# Wii_Board.net
KiCad netlist of a schematic drawn in EAGLE
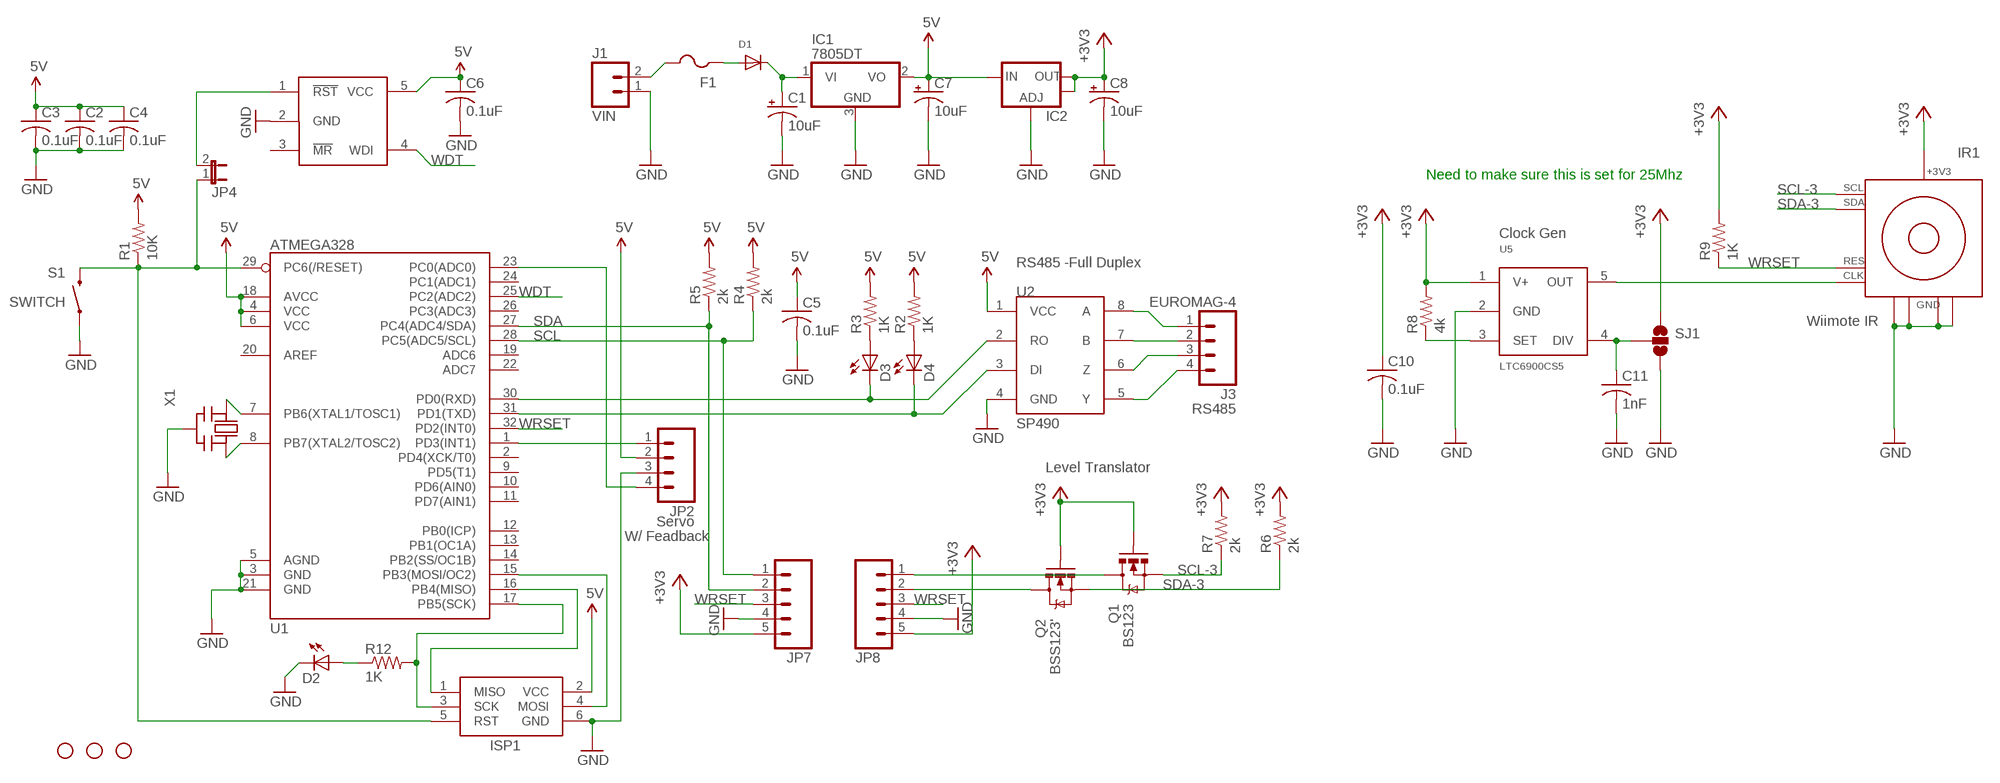
[diagram p0: schematic, sheet 1]

(export (version "E")
  (design (tool "Eeschema 10.0.6"))
  (components
    (comp (ref "C1")
      (value "10uF")
      (footprint "eagle-import:CT6032")
      (libsource (lib "eagle-import") (part "CPOL-USCT6032"))
    )
    (comp (ref "C2")
      (value "0.1uF")
      (footprint "eagle-import:C0805")
      (libsource (lib "eagle-import") (part "C-USC0805"))
    )
    (comp (ref "C3")
      (value "0.1uF")
      (footprint "eagle-import:C0805")
      (libsource (lib "eagle-import") (part "C-USC0805"))
    )
    (comp (ref "C4")
      (value "0.1uF")
      (footprint "eagle-import:C0805")
      (libsource (lib "eagle-import") (part "C-USC0805"))
    )
    (comp (ref "C5")
      (value "0.1uF")
      (footprint "eagle-import:C0805")
      (libsource (lib "eagle-import") (part "C-USC0805"))
    )
    (comp (ref "C6")
      (value "0.1uF")
      (footprint "eagle-import:C0805")
      (libsource (lib "eagle-import") (part "C-USC0805"))
    )
    (comp (ref "C7")
      (value "10uF")
      (footprint "eagle-import:CT3216")
      (libsource (lib "eagle-import") (part "CPOL-USCT3216"))
    )
    (comp (ref "C8")
      (value "10uF")
      (footprint "eagle-import:CT3528")
      (libsource (lib "eagle-import") (part "CPOL-USCT3528"))
    )
    (comp (ref "C10")
      (value "0.1uF")
      (footprint "eagle-import:C0805")
      (libsource (lib "eagle-import") (part "C-USC0805"))
    )
    (comp (ref "C11")
      (value "1nF")
      (footprint "eagle-import:C0805")
      (libsource (lib "eagle-import") (part "C-USC0805"))
    )
    (comp (ref "D1")
      (value "DIODESMA")
      (footprint "eagle-import:SMADIODE")
      (libsource (lib "eagle-import") (part "DIODESMA"))
    )
    (comp (ref "D2")
      (value "LEDCHIPLED_0805")
      (footprint "eagle-import:CHIPLED_0805")
      (libsource (lib "eagle-import") (part "LEDCHIPLED_0805"))
    )
    (comp (ref "D3")
      (value "LEDCHIPLED_0805")
      (footprint "eagle-import:CHIPLED_0805")
      (libsource (lib "eagle-import") (part "LEDCHIPLED_0805"))
    )
    (comp (ref "D4")
      (value "LEDCHIPLED_0805")
      (footprint "eagle-import:CHIPLED_0805")
      (libsource (lib "eagle-import") (part "LEDCHIPLED_0805"))
    )
    (comp (ref "F1")
      (value "PTCFUSE-1206")
      (footprint "eagle-import:R1206")
      (libsource (lib "eagle-import") (part "PTCFUSE-1206"))
    )
    (comp (ref "IC1")
      (value "7805DT")
      (footprint "eagle-import:TO252")
      (libsource (lib "eagle-import") (part "78DT05"))
    )
    (comp (ref "IC2")
      (value "V_REG_LM1117SOT223")
      (footprint "eagle-import:SOT223")
      (libsource (lib "eagle-import") (part "V_REG_LM1117SOT223"))
    )
    (comp (ref "IR1")
      (value "Wiimote IR")
      (footprint "eagle-import:WII_IR_SENSOR")
      (libsource (lib "eagle-import") (part "WII_IR_SENSOR"))
    )
    (comp (ref "ISP1")
      (value "AVRISP-6")
      (footprint "eagle-import:AVRISP")
      (libsource (lib "eagle-import") (part "AVRISP-6"))
    )
    (comp (ref "J1")
      (value "VIN")
      (footprint "eagle-import:M2")
      (libsource (lib "eagle-import") (part "EUROMAG-290DEG"))
    )
    (comp (ref "J3")
      (value "EUROMAG-4")
      (footprint "eagle-import:M4")
      (libsource (lib "eagle-import") (part "EUROMAG-4"))
    )
    (comp (ref "JP1")
      (value "STAND-OFF")
      (footprint "eagle-import:STAND-OFF")
      (libsource (lib "eagle-import") (part "STAND-OFF"))
    )
    (comp (ref "JP2")
      (value "M04LOCK")
      (footprint "eagle-import:1X04_LOCK")
      (libsource (lib "eagle-import") (part "M04LOCK"))
    )
    (comp (ref "JP3")
      (value "STAND-OFF")
      (footprint "eagle-import:STAND-OFF")
      (libsource (lib "eagle-import") (part "STAND-OFF"))
    )
    (comp (ref "JP4")
      (value "JUMPER-2SMD-NO")
      (footprint "eagle-import:SJ_2S-NO")
      (libsource (lib "eagle-import") (part "JUMPER-2SMD-NO"))
    )
    (comp (ref "JP5")
      (value "STAND-OFF")
      (footprint "eagle-import:STAND-OFF")
      (libsource (lib "eagle-import") (part "STAND-OFF"))
    )
    (comp (ref "JP7")
      (value "M05LOCK_LONGPADS")
      (footprint "eagle-import:1X05_LOCK_LONGPADS")
      (libsource (lib "eagle-import") (part "M05LOCK_LONGPADS"))
    )
    (comp (ref "JP8")
      (value "M05LOCK_LONGPADS")
      (footprint "eagle-import:1X05_LOCK_LONGPADS")
      (libsource (lib "eagle-import") (part "M05LOCK_LONGPADS"))
    )
    (comp (ref "Q1")
      (value "BS123")
      (footprint "eagle-import:SOT23")
      (libsource (lib "eagle-import") (part "MOSFET-NCHANNELBSS123LT1G"))
    )
    (comp (ref "Q2")
      (value "BSS123'")
      (footprint "eagle-import:SOT23")
      (libsource (lib "eagle-import") (part "MOSFET-NCHANNELBSS123LT1G"))
    )
    (comp (ref "R1")
      (value "10K")
      (footprint "eagle-import:M0805")
      (libsource (lib "eagle-import") (part "R-US_M0805"))
    )
    (comp (ref "R2")
      (value "1K")
      (footprint "eagle-import:M0805")
      (libsource (lib "eagle-import") (part "R-US_M0805"))
    )
    (comp (ref "R3")
      (value "1K")
      (footprint "eagle-import:M0805")
      (libsource (lib "eagle-import") (part "R-US_M0805"))
    )
    (comp (ref "R4")
      (value "2k")
      (footprint "eagle-import:M0805")
      (libsource (lib "eagle-import") (part "R-US_M0805"))
    )
    (comp (ref "R5")
      (value "2k")
      (footprint "eagle-import:M0805")
      (libsource (lib "eagle-import") (part "R-US_M0805"))
    )
    (comp (ref "R6")
      (value "2k")
      (footprint "eagle-import:M0805")
      (libsource (lib "eagle-import") (part "R-US_M0805"))
    )
    (comp (ref "R7")
      (value "2k")
      (footprint "eagle-import:M0805")
      (libsource (lib "eagle-import") (part "R-US_M0805"))
    )
    (comp (ref "R8")
      (value "4k")
      (footprint "eagle-import:M0805")
      (libsource (lib "eagle-import") (part "R-US_M0805"))
    )
    (comp (ref "R9")
      (value "1K")
      (footprint "eagle-import:M0805")
      (libsource (lib "eagle-import") (part "R-US_M0805"))
    )
    (comp (ref "R12")
      (value "1K")
      (footprint "eagle-import:M0805")
      (libsource (lib "eagle-import") (part "R-US_M0805"))
    )
    (comp (ref "S1")
      (value "SWITCH")
      (footprint "eagle-import:TACTILE-PTH")
      (libsource (lib "eagle-import") (part "SWITCH-MOMENTARY-2PTH"))
    )
    (comp (ref "SJ1")
      (value "SOLDERJUMPER_2WAYS")
      (footprint "eagle-import:SJ_3")
      (libsource (lib "eagle-import") (part "SOLDERJUMPER_2WAYS"))
    )
    (comp (ref "U1")
      (value "ATMEGA328")
      (footprint "eagle-import:TQFP32-08")
      (libsource (lib "eagle-import") (part "ATMEGA168"))
    )
    (comp (ref "U2")
      (value "SP490")
      (footprint "eagle-import:SO08")
      (libsource (lib "eagle-import") (part "ISL83077"))
    )
    (comp (ref "U3")
      (value "MAX823")
      (footprint "eagle-import:SOT23-5L")
      (libsource (lib "eagle-import") (part "MAX823"))
    )
    (comp (ref "U5")
      (value "LTC6900CS5")
      (footprint "eagle-import:TSOT-23-5")
      (libsource (lib "eagle-import") (part "LTC6900CS5"))
    )
    (comp (ref "X1")
      (value "CERMOSCILL-AWCSR")
      (footprint "eagle-import:AWCSR")
      (libsource (lib "eagle-import") (part "CERMOSCILL-AWCSR"))
    )
  )
  (nets
    (net (code "1") (name "+3V3") (class "Default")
      (node (ref "C10") (pin "1") (pinfunction "1_1") (pintype "passive"))
      (node (ref "C8") (pin "+") (pinfunction "+_+") (pintype "passive"))
      (node (ref "IC2") (pin "2") (pinfunction "OUT_2") (pintype "output"))
      (node (ref "IC2") (pin "4") (pinfunction "OUT_4") (pintype "output"))
      (node (ref "IR1") (pin "1_+3V3") (pinfunction "+3V3_1_+3V3") (pintype "bidirectional"))
      (node (ref "JP7") (pin "5") (pinfunction "5_5") (pintype "passive"))
      (node (ref "JP8") (pin "5") (pinfunction "5_5") (pintype "passive"))
      (node (ref "Q1") (pin "1") (pinfunction "G_1") (pintype "passive"))
      (node (ref "Q2") (pin "1") (pinfunction "G_1") (pintype "passive"))
      (node (ref "R6") (pin "2") (pinfunction "2_2") (pintype "passive"))
      (node (ref "R7") (pin "2") (pinfunction "2_2") (pintype "passive"))
      (node (ref "R8") (pin "2") (pinfunction "2_2") (pintype "passive"))
      (node (ref "R9") (pin "2") (pinfunction "2_2") (pintype "passive"))
      (node (ref "SJ1") (pin "1") (pinfunction "1_1") (pintype "passive"))
      (node (ref "U5") (pin "1") (pinfunction "V+_1") (pintype "bidirectional"))
    )
    (net (code "2") (name "/SCL") (class "Default")
      (node (ref "JP7") (pin "1") (pinfunction "1_1") (pintype "passive"))
      (node (ref "R4") (pin "1") (pinfunction "1_1") (pintype "passive"))
      (node (ref "U1") (pin "28") (pinfunction "PC5(ADC5/SCL)_28") (pintype "bidirectional"))
    )
    (net (code "3") (name "/SCL-3") (class "Default")
      (node (ref "IR1") (pin "5_SCL") (pinfunction "SCL_5_SCL") (pintype "bidirectional"))
      (node (ref "Q1") (pin "2") (pinfunction "S_2") (pintype "passive"))
      (node (ref "R7") (pin "1") (pinfunction "1_1") (pintype "passive"))
    )
    (net (code "4") (name "/SDA") (class "Default")
      (node (ref "JP7") (pin "2") (pinfunction "2_2") (pintype "passive"))
      (node (ref "R5") (pin "1") (pinfunction "1_1") (pintype "passive"))
      (node (ref "U1") (pin "27") (pinfunction "PC4(ADC4/SDA)_27") (pintype "bidirectional"))
    )
    (net (code "5") (name "/SDA-3") (class "Default")
      (node (ref "IR1") (pin "6_SDA") (pinfunction "SDA_6_SDA") (pintype "bidirectional"))
      (node (ref "Q2") (pin "2") (pinfunction "S_2") (pintype "passive"))
      (node (ref "R6") (pin "1") (pinfunction "1_1") (pintype "passive"))
    )
    (net (code "6") (name "/WDT") (class "Default")
      (node (ref "U1") (pin "25") (pinfunction "PC2(ADC2)_25") (pintype "bidirectional"))
      (node (ref "U3") (pin "4") (pinfunction "WDI_4") (pintype "bidirectional"))
    )
    (net (code "7") (name "/WRSET") (class "Default")
      (node (ref "IR1") (pin "8_RESET") (pinfunction "RES_8_RESET") (pintype "bidirectional"))
      (node (ref "JP7") (pin "3") (pinfunction "3_3") (pintype "passive"))
      (node (ref "JP8") (pin "3") (pinfunction "3_3") (pintype "passive"))
      (node (ref "R9") (pin "1") (pinfunction "1_1") (pintype "passive"))
      (node (ref "U1") (pin "32") (pinfunction "PD2(INT0)_32") (pintype "bidirectional"))
    )
    (net (code "8") (name "5V") (class "Default")
      (node (ref "C2") (pin "1") (pinfunction "1_1") (pintype "passive"))
      (node (ref "C3") (pin "1") (pinfunction "1_1") (pintype "passive"))
      (node (ref "C4") (pin "1") (pinfunction "1_1") (pintype "passive"))
      (node (ref "C5") (pin "1") (pinfunction "1_1") (pintype "passive"))
      (node (ref "C6") (pin "1") (pinfunction "1_1") (pintype "passive"))
      (node (ref "C7") (pin "+") (pinfunction "+_+") (pintype "passive"))
      (node (ref "IC1") (pin "2") (pinfunction "VO_2") (pintype "passive"))
      (node (ref "IC2") (pin "3") (pinfunction "IN_3") (pintype "input"))
      (node (ref "ISP1") (pin "2") (pinfunction "VCC_2") (pintype "power_in"))
      (node (ref "JP2") (pin "2") (pinfunction "2_2") (pintype "passive"))
      (node (ref "R1") (pin "2") (pinfunction "2_2") (pintype "passive"))
      (node (ref "R2") (pin "2") (pinfunction "2_2") (pintype "passive"))
      (node (ref "R3") (pin "2") (pinfunction "2_2") (pintype "passive"))
      (node (ref "R4") (pin "2") (pinfunction "2_2") (pintype "passive"))
      (node (ref "R5") (pin "2") (pinfunction "2_2") (pintype "passive"))
      (node (ref "U1") (pin "18") (pinfunction "AVCC_18") (pintype "bidirectional"))
      (node (ref "U1") (pin "4") (pinfunction "VCC_4") (pintype "bidirectional"))
      (node (ref "U1") (pin "6") (pinfunction "VCC_6") (pintype "bidirectional"))
      (node (ref "U2") (pin "1") (pinfunction "VCC_1") (pintype "bidirectional"))
      (node (ref "U3") (pin "5") (pinfunction "VCC_5") (pintype "bidirectional"))
    )
    (net (code "9") (name "GND") (class "Default")
      (node (ref "C1") (pin "-") (pinfunction "-_-") (pintype "passive"))
      (node (ref "C10") (pin "2") (pinfunction "2_2") (pintype "passive"))
      (node (ref "C11") (pin "2") (pinfunction "2_2") (pintype "passive"))
      (node (ref "C2") (pin "2") (pinfunction "2_2") (pintype "passive"))
      (node (ref "C3") (pin "2") (pinfunction "2_2") (pintype "passive"))
      (node (ref "C4") (pin "2") (pinfunction "2_2") (pintype "passive"))
      (node (ref "C5") (pin "2") (pinfunction "2_2") (pintype "passive"))
      (node (ref "C6") (pin "2") (pinfunction "2_2") (pintype "passive"))
      (node (ref "C7") (pin "-") (pinfunction "-_-") (pintype "passive"))
      (node (ref "C8") (pin "-") (pinfunction "-_-") (pintype "passive"))
      (node (ref "D2") (pin "C") (pinfunction "C_C") (pintype "passive"))
      (node (ref "IC1") (pin "3") (pinfunction "GND_3") (pintype "passive"))
      (node (ref "IC2") (pin "1") (pinfunction "ADJ_1") (pintype "input"))
      (node (ref "IR1") (pin "2_GND@1") (pinfunction "GND_2_GND@1") (pintype "bidirectional"))
      (node (ref "IR1") (pin "3_GND@2") (pinfunction "GND_3_GND@2") (pintype "bidirectional"))
      (node (ref "IR1") (pin "GND@3") (pinfunction "GND_GND@3") (pintype "bidirectional"))
      (node (ref "IR1") (pin "GND@4") (pinfunction "GND_GND@4") (pintype "bidirectional"))
      (node (ref "ISP1") (pin "6") (pinfunction "GND_6") (pintype "power_in"))
      (node (ref "J1") (pin "1") (pinfunction "1_1") (pintype "passive"))
      (node (ref "JP2") (pin "3") (pinfunction "3_3") (pintype "passive"))
      (node (ref "JP7") (pin "4") (pinfunction "4_4") (pintype "passive"))
      (node (ref "JP8") (pin "4") (pinfunction "4_4") (pintype "passive"))
      (node (ref "S1") (pin "1") (pinfunction "1_1") (pintype "passive"))
      (node (ref "SJ1") (pin "3") (pinfunction "3_3") (pintype "passive"))
      (node (ref "U1") (pin "21") (pinfunction "GND_21") (pintype "bidirectional"))
      (node (ref "U1") (pin "3") (pinfunction "GND_3") (pintype "bidirectional"))
      (node (ref "U1") (pin "5") (pinfunction "AGND_5") (pintype "bidirectional"))
      (node (ref "U2") (pin "4") (pinfunction "GND_4") (pintype "bidirectional"))
      (node (ref "U3") (pin "2") (pinfunction "GND_2") (pintype "bidirectional"))
      (node (ref "U5") (pin "2") (pinfunction "GND_2") (pintype "bidirectional"))
      (node (ref "X1") (pin "2") (pinfunction "GND_2") (pintype "bidirectional"))
    )
    (net (code "10") (name "Net-(D1-PadA)") (class "Default")
      (node (ref "D1") (pin "A") (pinfunction "A_A") (pintype "passive"))
      (node (ref "F1") (pin "1") (pinfunction "1_1") (pintype "passive"))
    )
    (net (code "11") (name "Net-(D2-PadA)") (class "Default")
      (node (ref "D2") (pin "A") (pinfunction "A_A") (pintype "passive"))
      (node (ref "R12") (pin "1") (pinfunction "1_1") (pintype "passive"))
    )
    (net (code "12") (name "Net-(D3-PadA)") (class "Default")
      (node (ref "D3") (pin "A") (pinfunction "A_A") (pintype "passive"))
      (node (ref "R3") (pin "1") (pinfunction "1_1") (pintype "passive"))
    )
    (net (code "13") (name "Net-(D4-PadA)") (class "Default")
      (node (ref "D4") (pin "A") (pinfunction "A_A") (pintype "passive"))
      (node (ref "R2") (pin "1") (pinfunction "1_1") (pintype "passive"))
    )
    (net (code "14") (name "Net-(F1-Pad2)") (class "Default")
      (node (ref "F1") (pin "2") (pinfunction "2_2") (pintype "passive"))
      (node (ref "J1") (pin "2") (pinfunction "2_2") (pintype "passive"))
    )
    (net (code "15") (name "Net-(IC1-VI)") (class "Default")
      (node (ref "C1") (pin "+") (pinfunction "+_+") (pintype "passive"))
      (node (ref "D1") (pin "C") (pinfunction "C_C") (pintype "passive"))
      (node (ref "IC1") (pin "1") (pinfunction "VI_1") (pintype "input"))
    )
    (net (code "16") (name "Net-(IR1-CLK)") (class "Default")
      (node (ref "IR1") (pin "7_CLK") (pinfunction "CLK_7_CLK") (pintype "bidirectional"))
      (node (ref "U5") (pin "5") (pinfunction "OUT_5") (pintype "bidirectional"))
    )
    (net (code "17") (name "Net-(ISP1-MISO)") (class "Default")
      (node (ref "ISP1") (pin "1") (pinfunction "MISO_1") (pintype "input"))
      (node (ref "U1") (pin "16") (pinfunction "PB4(MISO)_16") (pintype "bidirectional"))
    )
    (net (code "18") (name "Net-(ISP1-MOSI)") (class "Default")
      (node (ref "ISP1") (pin "4") (pinfunction "MOSI_4") (pintype "output"))
      (node (ref "U1") (pin "15") (pinfunction "PB3(MOSI/OC2)_15") (pintype "bidirectional"))
    )
    (net (code "19") (name "Net-(ISP1-RST)") (class "Default")
      (node (ref "ISP1") (pin "5") (pinfunction "RST_5") (pintype "output"))
      (node (ref "JP4") (pin "1") (pinfunction "1_1") (pintype "passive"))
      (node (ref "R1") (pin "1") (pinfunction "1_1") (pintype "passive"))
      (node (ref "S1") (pin "3") (pinfunction "2_3") (pintype "passive"))
      (node (ref "U1") (pin "29") (pinfunction "PC6(/RESET)_29") (pintype "bidirectional"))
    )
    (net (code "20") (name "Net-(ISP1-SCK)") (class "Default")
      (node (ref "ISP1") (pin "3") (pinfunction "SCK_3") (pintype "output"))
      (node (ref "R12") (pin "2") (pinfunction "2_2") (pintype "passive"))
      (node (ref "U1") (pin "17") (pinfunction "PB5(SCK)_17") (pintype "bidirectional"))
    )
    (net (code "21") (name "Net-(Q1-D)") (class "Default")
      (node (ref "JP8") (pin "1") (pinfunction "1_1") (pintype "passive"))
      (node (ref "Q1") (pin "3") (pinfunction "D_3") (pintype "passive"))
    )
    (net (code "22") (name "Net-(Q2-D)") (class "Default")
      (node (ref "JP8") (pin "2") (pinfunction "2_2") (pintype "passive"))
      (node (ref "Q2") (pin "3") (pinfunction "D_3") (pintype "passive"))
    )
    (net (code "23") (name "Net-(U1-PB6(XTAL1{slash}TOSC1))") (class "Default")
      (node (ref "U1") (pin "7") (pinfunction "PB6(XTAL1/TOSC1)_7") (pintype "bidirectional"))
      (node (ref "X1") (pin "1") (pinfunction "IN_1") (pintype "bidirectional"))
    )
    (net (code "24") (name "Net-(U1-PB7(XTAL2{slash}TOSC2))") (class "Default")
      (node (ref "U1") (pin "8") (pinfunction "PB7(XTAL2/TOSC2)_8") (pintype "bidirectional"))
      (node (ref "X1") (pin "3") (pinfunction "OUT_3") (pintype "bidirectional"))
    )
    (net (code "25") (name "Net-(U1-PC0(ADC0))") (class "Default")
      (node (ref "JP2") (pin "4") (pinfunction "4_4") (pintype "passive"))
      (node (ref "U1") (pin "23") (pinfunction "PC0(ADC0)_23") (pintype "bidirectional"))
    )
    (net (code "26") (name "Net-(U1-PD0(RXD))") (class "Default")
      (node (ref "D3") (pin "C") (pinfunction "C_C") (pintype "passive"))
      (node (ref "U1") (pin "30") (pinfunction "PD0(RXD)_30") (pintype "bidirectional"))
      (node (ref "U2") (pin "2") (pinfunction "RO_2") (pintype "bidirectional"))
    )
    (net (code "27") (name "Net-(U1-PD1(TXD))") (class "Default")
      (node (ref "D4") (pin "C") (pinfunction "C_C") (pintype "passive"))
      (node (ref "U1") (pin "31") (pinfunction "PD1(TXD)_31") (pintype "bidirectional"))
      (node (ref "U2") (pin "3") (pinfunction "DI_3") (pintype "bidirectional"))
    )
    (net (code "28") (name "Net-(U1-PD3(INT1))") (class "Default")
      (node (ref "JP2") (pin "1") (pinfunction "1_1") (pintype "passive"))
      (node (ref "U1") (pin "1") (pinfunction "PD3(INT1)_1") (pintype "bidirectional"))
    )
    (net (code "29") (name "Net-(U2-A)") (class "Default")
      (node (ref "J3") (pin "1") (pinfunction "1_1") (pintype "passive"))
      (node (ref "U2") (pin "8") (pinfunction "A_8") (pintype "bidirectional"))
    )
    (net (code "30") (name "Net-(U2-B)") (class "Default")
      (node (ref "J3") (pin "2") (pinfunction "2_2") (pintype "passive"))
      (node (ref "U2") (pin "7") (pinfunction "B_7") (pintype "bidirectional"))
    )
    (net (code "31") (name "Net-(U2-Y)") (class "Default")
      (node (ref "J3") (pin "4") (pinfunction "4_4") (pintype "passive"))
      (node (ref "U2") (pin "5") (pinfunction "Y_5") (pintype "bidirectional"))
    )
    (net (code "32") (name "Net-(U2-Z)") (class "Default")
      (node (ref "J3") (pin "3") (pinfunction "3_3") (pintype "passive"))
      (node (ref "U2") (pin "6") (pinfunction "Z_6") (pintype "bidirectional"))
    )
    (net (code "33") (name "Net-(U3-~{RST})") (class "Default")
      (node (ref "JP4") (pin "2") (pinfunction "2_2") (pintype "passive"))
      (node (ref "U3") (pin "1") (pinfunction "~{RST}_1") (pintype "bidirectional"))
    )
    (net (code "34") (name "Net-(U5-DIV)") (class "Default")
      (node (ref "C11") (pin "1") (pinfunction "1_1") (pintype "passive"))
      (node (ref "SJ1") (pin "2") (pinfunction "2_2") (pintype "passive"))
      (node (ref "U5") (pin "4") (pinfunction "DIV_4") (pintype "bidirectional"))
    )
    (net (code "35") (name "Net-(U5-SET)") (class "Default")
      (node (ref "R8") (pin "1") (pinfunction "1_1") (pintype "passive"))
      (node (ref "U5") (pin "3") (pinfunction "SET_3") (pintype "bidirectional"))
    )
    (net (code "36") (name "unconnected-(U1-ADC6-Pad19)") (class "Default")
      (node (ref "U1") (pin "19") (pinfunction "ADC6_19") (pintype "bidirectional"))
    )
    (net (code "37") (name "unconnected-(U1-ADC7-Pad22)") (class "Default")
      (node (ref "U1") (pin "22") (pinfunction "ADC7_22") (pintype "bidirectional"))
    )
    (net (code "38") (name "unconnected-(U1-AREF-Pad20)") (class "Default")
      (node (ref "U1") (pin "20") (pinfunction "AREF_20") (pintype "bidirectional"))
    )
    (net (code "39") (name "unconnected-(U1-PB0(ICP)-Pad12)") (class "Default")
      (node (ref "U1") (pin "12") (pinfunction "PB0(ICP)_12") (pintype "bidirectional"))
    )
    (net (code "40") (name "unconnected-(U1-PB1(OC1A)-Pad13)") (class "Default")
      (node (ref "U1") (pin "13") (pinfunction "PB1(OC1A)_13") (pintype "bidirectional"))
    )
    (net (code "41") (name "unconnected-(U1-PB2(SS{slash}OC1B)-Pad14)") (class "Default")
      (node (ref "U1") (pin "14") (pinfunction "PB2(SS/OC1B)_14") (pintype "bidirectional"))
    )
    (net (code "42") (name "unconnected-(U1-PC1(ADC1)-Pad24)") (class "Default")
      (node (ref "U1") (pin "24") (pinfunction "PC1(ADC1)_24") (pintype "bidirectional"))
    )
    (net (code "43") (name "unconnected-(U1-PC3(ADC3)-Pad26)") (class "Default")
      (node (ref "U1") (pin "26") (pinfunction "PC3(ADC3)_26") (pintype "bidirectional"))
    )
    (net (code "44") (name "unconnected-(U1-PD4(XCK{slash}T0)-Pad2)") (class "Default")
      (node (ref "U1") (pin "2") (pinfunction "PD4(XCK/T0)_2") (pintype "bidirectional"))
    )
    (net (code "45") (name "unconnected-(U1-PD5(T1)-Pad9)") (class "Default")
      (node (ref "U1") (pin "9") (pinfunction "PD5(T1)_9") (pintype "bidirectional"))
    )
    (net (code "46") (name "unconnected-(U1-PD6(AIN0)-Pad10)") (class "Default")
      (node (ref "U1") (pin "10") (pinfunction "PD6(AIN0)_10") (pintype "bidirectional"))
    )
    (net (code "47") (name "unconnected-(U1-PD7(AIN1)-Pad11)") (class "Default")
      (node (ref "U1") (pin "11") (pinfunction "PD7(AIN1)_11") (pintype "bidirectional"))
    )
    (net (code "48") (name "unconnected-(U3-~{MR}-Pad3)") (class "Default")
      (node (ref "U3") (pin "3") (pinfunction "~{MR}_3") (pintype "bidirectional"))
    )
  )
)
